# Artic.net
KiCad netlist of a schematic drawn in Altium Designer
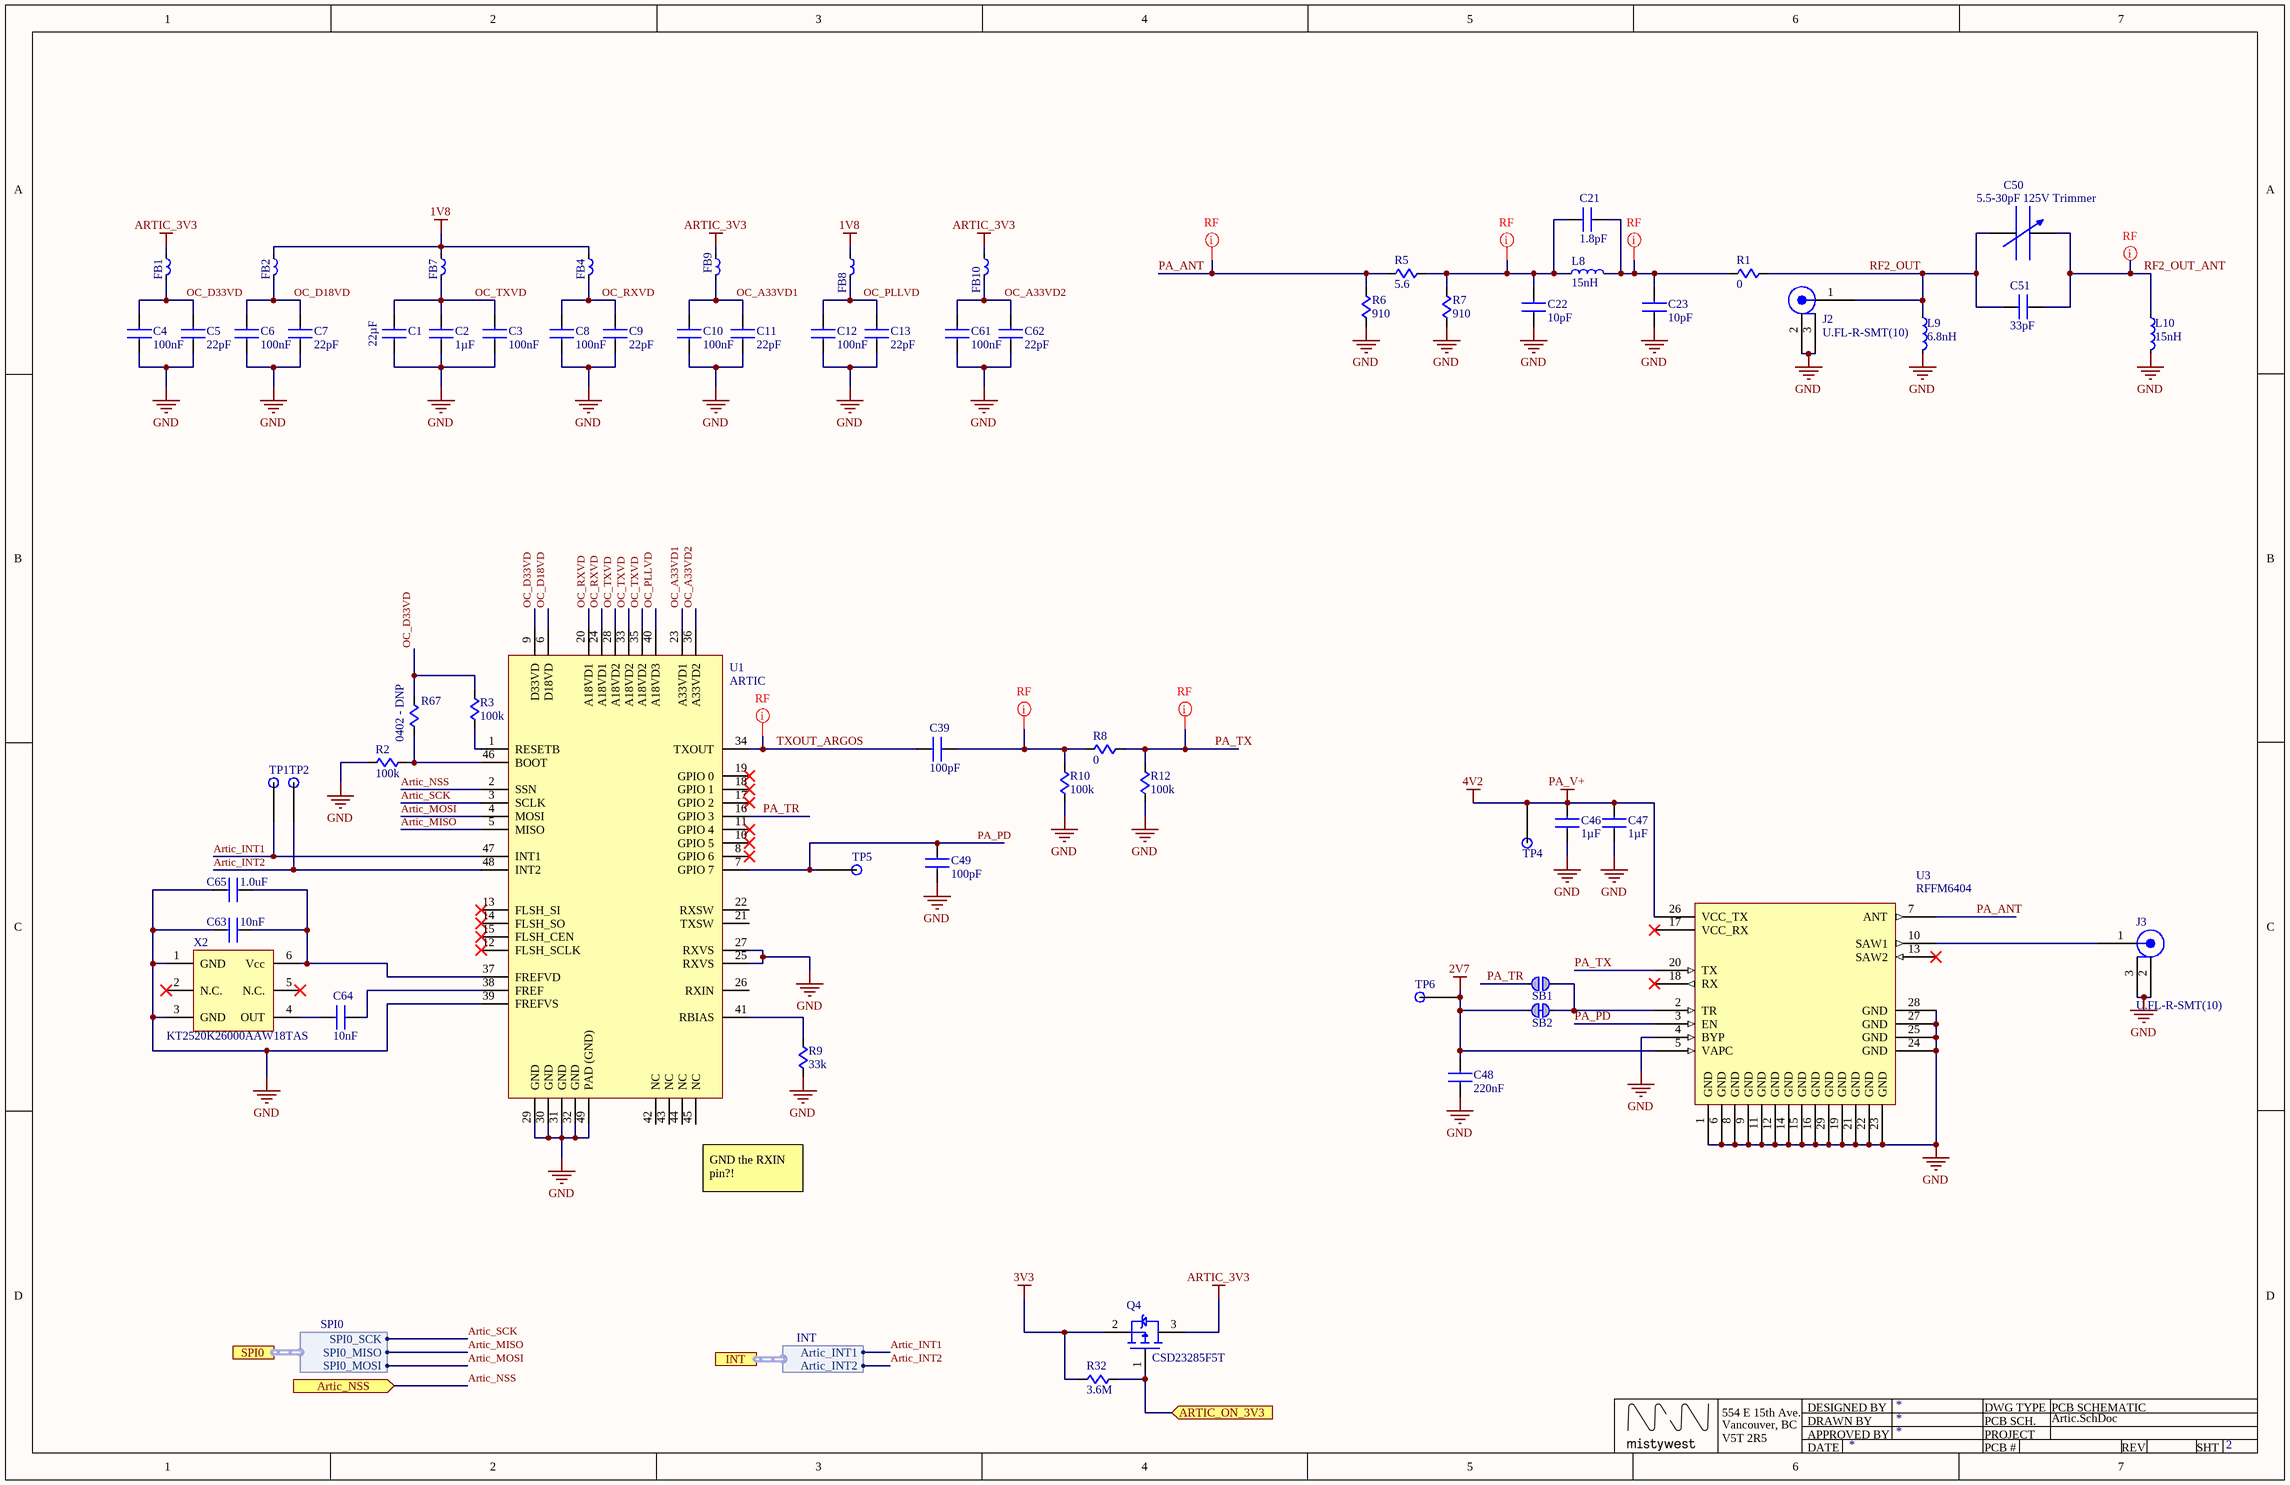
[diagram p0: Artic.SchDoc]

(export (version "E")
  (design (tool "Eeschema 10.0.6"))
  (components
    (comp (ref "C1")
      (value "22µF")
      (footprint "CAPC1608N-0603")
      (description "CAP CER 22UF 6.3V X5R 0603 ±10%")
      (fields
        (field (name "MANUFACTURER") "Samsung Electro-Mechanics America, Inc.")
        (field (name "MANUFACTURER PART NUMBER") "CL10A226KQ8NRNE")
      )
      (libsource (lib "Misty West") (part "Component_1"))
    )
    (comp (ref "C2")
      (value "1µF")
      (footprint "CAPC1005N-0402")
      (description "CAP CER 1UF 6.3V X7R 0402 ±10%")
      (fields
        (field (name "MANUFACTURER") "Samsung Electro-Mechanics America, Inc.")
        (field (name "MANUFACTURER PART NUMBER") "CL05B105KQ5NQNC")
      )
      (libsource (lib "Misty West") (part "Component_1"))
    )
    (comp (ref "C3")
      (value "100nF")
      (footprint "CAPC1005N-0402")
      (description "CAP CER 0.1UF 10V X7R 0402 ±5%")
      (fields
        (field (name "MANUFACTURER") "Samsung Electro-Mechanics America, Inc.")
        (field (name "MANUFACTURER PART NUMBER") "CL05B104JP5NNNC")
      )
      (libsource (lib "Misty West") (part "Component_1"))
    )
    (comp (ref "C4")
      (value "100nF")
      (footprint "CAPC1005N-0402")
      (description "CAP CER 0.1UF 10V X7R 0402 ±5%")
      (fields
        (field (name "MANUFACTURER") "Samsung Electro-Mechanics America, Inc.")
        (field (name "MANUFACTURER PART NUMBER") "CL05B104JP5NNNC")
      )
      (libsource (lib "Misty West") (part "Component_1"))
    )
    (comp (ref "C5")
      (value "22pF")
      (footprint "CAPC1005N-0402")
      (description "CAP CER 22PF 50V C0G/NP0 0402 ±5%")
      (fields
        (field (name "MANUFACTURER") "Samsung Electro-Mechanics America, Inc.")
        (field (name "MANUFACTURER PART NUMBER") "CL05C220JB5NNNC")
      )
      (libsource (lib "Misty West") (part "Component_1"))
    )
    (comp (ref "C6")
      (value "100nF")
      (footprint "CAPC1005N-0402")
      (description "CAP CER 0.1UF 10V X7R 0402 ±5%")
      (fields
        (field (name "MANUFACTURER") "Samsung Electro-Mechanics America, Inc.")
        (field (name "MANUFACTURER PART NUMBER") "CL05B104JP5NNNC")
      )
      (libsource (lib "Misty West") (part "Component_1"))
    )
    (comp (ref "C7")
      (value "22pF")
      (footprint "CAPC1005N-0402")
      (description "CAP CER 22PF 50V C0G/NP0 0402 ±5%")
      (fields
        (field (name "MANUFACTURER") "Samsung Electro-Mechanics America, Inc.")
        (field (name "MANUFACTURER PART NUMBER") "CL05C220JB5NNNC")
      )
      (libsource (lib "Misty West") (part "Component_1"))
    )
    (comp (ref "C8")
      (value "100nF")
      (footprint "CAPC1005N-0402")
      (description "CAP CER 0.1UF 10V X7R 0402 ±5%")
      (fields
        (field (name "MANUFACTURER") "Samsung Electro-Mechanics America, Inc.")
        (field (name "MANUFACTURER PART NUMBER") "CL05B104JP5NNNC")
      )
      (libsource (lib "Misty West") (part "Component_1"))
    )
    (comp (ref "C9")
      (value "22pF")
      (footprint "CAPC1005N-0402")
      (description "CAP CER 22PF 50V C0G/NP0 0402 ±5%")
      (fields
        (field (name "MANUFACTURER") "Samsung Electro-Mechanics America, Inc.")
        (field (name "MANUFACTURER PART NUMBER") "CL05C220JB5NNNC")
      )
      (libsource (lib "Misty West") (part "Component_1"))
    )
    (comp (ref "C10")
      (value "100nF")
      (footprint "CAPC1005N-0402")
      (description "CAP CER 0.1UF 10V X7R 0402 ±5%")
      (fields
        (field (name "MANUFACTURER") "Samsung Electro-Mechanics America, Inc.")
        (field (name "MANUFACTURER PART NUMBER") "CL05B104JP5NNNC")
      )
      (libsource (lib "Misty West") (part "Component_1"))
    )
    (comp (ref "C11")
      (value "22pF")
      (footprint "CAPC1005N-0402")
      (description "CAP CER 22PF 50V C0G/NP0 0402 ±5%")
      (fields
        (field (name "MANUFACTURER") "Samsung Electro-Mechanics America, Inc.")
        (field (name "MANUFACTURER PART NUMBER") "CL05C220JB5NNNC")
      )
      (libsource (lib "Misty West") (part "Component_1"))
    )
    (comp (ref "C12")
      (value "100nF")
      (footprint "CAPC1005N-0402")
      (description "CAP CER 0.1UF 10V X7R 0402 ±5%")
      (fields
        (field (name "MANUFACTURER") "Samsung Electro-Mechanics America, Inc.")
        (field (name "MANUFACTURER PART NUMBER") "CL05B104JP5NNNC")
      )
      (libsource (lib "Misty West") (part "Component_1"))
    )
    (comp (ref "C13")
      (value "22pF")
      (footprint "CAPC1005N-0402")
      (description "CAP CER 22PF 50V C0G/NP0 0402 ±5%")
      (fields
        (field (name "MANUFACTURER") "Samsung Electro-Mechanics America, Inc.")
        (field (name "MANUFACTURER PART NUMBER") "CL05C220JB5NNNC")
      )
      (libsource (lib "Misty West") (part "Component_1"))
    )
    (comp (ref "C21")
      (value "1.8pF")
      (footprint "CAPC1005N-0402")
      (description "CAP CER 1.8PF 50V C0G/NP0 0402 ±0.25pF")
      (fields
        (field (name "MANUFACTURER") "Samsung Electro-Mechanics America, Inc.")
        (field (name "MANUFACTURER PART NUMBER") "CL05C1R8CB5NNNC")
      )
      (libsource (lib "Misty West") (part "Component_1"))
    )
    (comp (ref "C22")
      (value "10pF")
      (footprint "CAPC1005N-0402")
      (description "CAP CER 10PF 50V C0G/NP0 0402 ±0.25pF")
      (fields
        (field (name "MANUFACTURER") "Samsung Electro-Mechanics America, Inc.")
        (field (name "MANUFACTURER PART NUMBER") "CL05C100CB5NNNC")
      )
      (libsource (lib "Misty West") (part "Component_1"))
    )
    (comp (ref "C23")
      (value "10pF")
      (footprint "CAPC1005N-0402")
      (description "CAP CER 10PF 50V C0G/NP0 0402 ±0.25pF")
      (fields
        (field (name "MANUFACTURER") "Samsung Electro-Mechanics America, Inc.")
        (field (name "MANUFACTURER PART NUMBER") "CL05C100CB5NNNC")
      )
      (libsource (lib "Misty West") (part "Component_1"))
    )
    (comp (ref "C39")
      (value "100pF")
      (footprint "CAPC1005N-0402")
      (description "CAP CER 100PF 50V C0G/NP0 0402 ±5% AEC-Q200")
      (fields
        (field (name "MANUFACTURER") "Samsung Electro-Mechanics America, Inc.")
        (field (name "MANUFACTURER PART NUMBER") "CL05C101JB51PNC")
      )
      (libsource (lib "Misty West") (part "Component_1"))
    )
    (comp (ref "C46")
      (value "1µF")
      (footprint "CAPC1005N-0402")
      (description "CAP CER 1UF 6.3V X7R 0402 ±10%")
      (fields
        (field (name "MANUFACTURER") "Samsung Electro-Mechanics America, Inc.")
        (field (name "MANUFACTURER PART NUMBER") "CL05B105KQ5NQNC")
      )
      (libsource (lib "Misty West") (part "Component_1"))
    )
    (comp (ref "C47")
      (value "1µF")
      (footprint "CAPC1005N-0402")
      (description "CAP CER 1UF 6.3V X7R 0402 ±10%")
      (fields
        (field (name "MANUFACTURER") "Samsung Electro-Mechanics America, Inc.")
        (field (name "MANUFACTURER PART NUMBER") "CL05B105KQ5NQNC")
      )
      (libsource (lib "Misty West") (part "Component_1"))
    )
    (comp (ref "C48")
      (value "220nF")
      (footprint "CAPC1005N-0402")
      (description "CAP CER 0.22UF 10V X7R 0402 ±10%")
      (fields
        (field (name "MANUFACTURER") "Samsung Electro-Mechanics America, Inc.")
        (field (name "MANUFACTURER PART NUMBER") "CL05B224KP5NNNC")
      )
      (libsource (lib "Misty West") (part "Component_1"))
    )
    (comp (ref "C49")
      (value "100pF")
      (footprint "CAPC1005N-0402")
      (description "CAP CER 100PF 50V C0G/NP0 0402 ±5% AEC-Q200")
      (fields
        (field (name "MANUFACTURER") "Samsung Electro-Mechanics America, Inc.")
        (field (name "MANUFACTURER PART NUMBER") "CL05C101JB51PNC")
      )
      (libsource (lib "Misty West") (part "Component_1"))
    )
    (comp (ref "C50")
      (value "5.5-30pF 125V Trimmer")
      (footprint "CAPC4531X17N")
      (description "CAP TRIMMER 5.5-30PF 125V SMD")
      (fields
        (field (name "MANUFACTURER") "Knowles Voltronics")
        (field (name "MANUFACTURER PART NUMBER") "JR300")
      )
      (libsource (lib "Misty West") (part "=Capacitance"))
    )
    (comp (ref "C51")
      (value "33pF")
      (footprint "CAPC1005N-0402")
      (description "CAP CER 33PF 50V C0G/NP0 0402 ±5%")
      (fields
        (field (name "TOLERANCE") "±5%")
        (field (name "VOLTAGE") "50V")
        (field (name "CAPACITANCE") "33pF")
      )
      (libsource (lib "Misty West") (part "Component_1"))
    )
    (comp (ref "C61")
      (value "100nF")
      (footprint "CAPC1005N-0402")
      (description "CAP CER 0.1UF 10V X7R 0402 ±5%")
      (fields
        (field (name "MANUFACTURER") "Samsung Electro-Mechanics America, Inc.")
        (field (name "MANUFACTURER PART NUMBER") "CL05B104JP5NNNC")
      )
      (libsource (lib "Misty West") (part "Component_1"))
    )
    (comp (ref "C62")
      (value "22pF")
      (footprint "CAPC1005N-0402")
      (description "CAP CER 22PF 50V C0G/NP0 0402 ±5%")
      (fields
        (field (name "MANUFACTURER") "Samsung Electro-Mechanics America, Inc.")
        (field (name "MANUFACTURER PART NUMBER") "CL05C220JB5NNNC")
      )
      (libsource (lib "Misty West") (part "Component_1"))
    )
    (comp (ref "C63")
      (value "10nF")
      (footprint "CAPC1005N-0402")
      (description "CAP CER 10000PF 10V X7R 0402 ±10%")
      (fields
        (field (name "MANUFACTURER") "Samsung Electro-Mechanics America, Inc.")
        (field (name "MANUFACTURER PART NUMBER") "CL05B103KP5NNNC")
      )
      (libsource (lib "Misty West") (part "Component_1"))
    )
    (comp (ref "C64")
      (value "10nF")
      (footprint "CAPC1005N-0402")
      (description "CAP CER 10000PF 10V X7R 0402 ±10%")
      (fields
        (field (name "MANUFACTURER") "Samsung Electro-Mechanics America, Inc.")
        (field (name "MANUFACTURER PART NUMBER") "CL05B103KP5NNNC")
      )
      (libsource (lib "Misty West") (part "Component_1"))
    )
    (comp (ref "C65")
      (value "1.0uF")
      (footprint "CAPC1608N-0603")
      (description "CAP CER 1.0uF 6.3V X7R 0603 ±10%")
      (fields
        (field (name "MANUFACTURER") "Samsung Electro-Mechanics America, Inc.")
        (field (name "MANUFACTURER PART NUMBER") "CL10B105KQ8NNN")
      )
      (libsource (lib "Misty West") (part "Component_1"))
    )
    (comp (ref "FB1")
      (value "BLM15AG221SN1D")
      (footprint "MURA-BLM15-CHIP-2_V")
      (fields (field (name "MANUFACTURER") "Murata"))
      (libsource (lib "Misty West") (part "CMP-04113-4"))
    )
    (comp (ref "FB2")
      (value "BLM15AG221SN1D")
      (footprint "MURA-BLM15-CHIP-2_V")
      (fields (field (name "MANUFACTURER") "Murata"))
      (libsource (lib "Misty West") (part "CMP-04113-4"))
    )
    (comp (ref "FB4")
      (value "BLM15AG221SN1D")
      (footprint "MURA-BLM15-CHIP-2_V")
      (fields (field (name "MANUFACTURER") "Murata"))
      (libsource (lib "Misty West") (part "CMP-04113-4"))
    )
    (comp (ref "FB7")
      (value "BLM15AG221SN1D")
      (footprint "MURA-BLM15-CHIP-2_V")
      (fields (field (name "MANUFACTURER") "Murata"))
      (libsource (lib "Misty West") (part "CMP-04113-4"))
    )
    (comp (ref "FB8")
      (value "BLM15AG221SN1D")
      (footprint "MURA-BLM15-CHIP-2_V")
      (fields (field (name "MANUFACTURER") "Murata"))
      (libsource (lib "Misty West") (part "CMP-04113-4"))
    )
    (comp (ref "FB9")
      (value "BLM15AG221SN1D")
      (footprint "MURA-BLM15-CHIP-2_V")
      (fields (field (name "MANUFACTURER") "Murata"))
      (libsource (lib "Misty West") (part "CMP-04113-4"))
    )
    (comp (ref "FB10")
      (value "BLM15AG221SN1D")
      (footprint "MURA-BLM15-CHIP-2_V")
      (fields (field (name "MANUFACTURER") "Murata"))
      (libsource (lib "Misty West") (part "CMP-04113-4"))
    )
    (comp (ref "J2")
      (value "CONNECTOR COAX-M 2GND")
      (footprint "con_hrs_U_FL-SMT")
      (description "CONN RECPT ULTRA-MINI COAX SMD")
      (fields
        (field (name "MFG") "HIROSE")
        (field (name "MFG_PN") "U.FL-R-SMT(10)")
        (field (name "MANUFACTURER PART NUMBER") "U.FL-R-SMT(10)")
      )
      (libsource (lib "Misty West") (part "CONNECTOR COAX-M 2GND"))
    )
    (comp (ref "J3")
      (value "CONNECTOR COAX-M 2GND")
      (footprint "con_hrs_U_FL-SMT")
      (description "CONN RECPT ULTRA-MINI COAX SMD")
      (fields
        (field (name "MFG") "HIROSE")
        (field (name "MFG_PN") "U.FL-R-SMT(10)")
        (field (name "MANUFACTURER PART NUMBER") "U.FL-R-SMT(10)")
      )
      (libsource (lib "Misty West") (part "CONNECTOR COAX-M 2GND"))
    )
    (comp (ref "L8")
      (value "15nH")
      (footprint "LQW2BA")
      (description "FIXED IND 15NH 1.5A 120 MOHM")
      (fields
        (field (name "MANUFACTURER") "MuRata")
        (field (name "MANUFACTURER PART NUMBER") "LQW2BAN15NG00L")
      )
      (libsource (lib "") (part "Component_1_3"))
    )
    (comp (ref "L9")
      (value "6.8nH")
      (footprint "0603HP")
      (description "0603HP-6N8X_E_")
      (fields (field (name "MANUFACTURER") "Coilcraft"))
      (libsource (lib "") (part "Component_1_3"))
    )
    (comp (ref "L10")
      (value "15nH")
      (footprint "0603HP")
      (description "0603HP-15NX_E_")
      (fields (field (name "MANUFACTURER") "Coilcraft"))
      (libsource (lib "") (part "Component_1_3"))
    )
    (comp (ref "Q4")
      (value "CSD23285F5T")
      (footprint "3-XFDFN")
      (description "P-Channel 12V 5.4A (Ta) 500mW (Ta) Surface Mount 3-PICOSTAR")
      (fields (field (name "MANUFACTURER") "Texas Instruments"))
      (libsource (lib "Misty West") (part "Mosfet-P-CH, 8Pin"))
    )
    (comp (ref "R1")
      (value "0")
      (footprint "RESC0402(1005)_N")
      (description "RES SMD 0.0OHM JUMPER 1/16W 0402")
      (fields
        (field (name "MANUFACTURER") "Yageo")
        (field (name "MANUFACTURER PART NUMBER") "RC0402JR-070RL")
      )
      (libsource (lib "") (part "Component_1_1"))
    )
    (comp (ref "R2")
      (value "100k")
      (footprint "RESC0402(1005)_N")
      (description "RES SMD 100K OHM 1% 1/10W 0402")
      (fields
        (field (name "MANUFACTURER") "Panasonic Electronic Components")
        (field (name "MANUFACTURER PART NUMBER") "ERJ-2RKF1003X")
      )
      (libsource (lib "") (part "Component_1_1"))
    )
    (comp (ref "R3")
      (value "100k")
      (footprint "RESC0402(1005)_N")
      (description "RES SMD 100K OHM 1% 1/10W 0402")
      (fields
        (field (name "MANUFACTURER") "Panasonic Electronic Components")
        (field (name "MANUFACTURER PART NUMBER") "ERJ-2RKF1003X")
      )
      (libsource (lib "") (part "Component_1_1"))
    )
    (comp (ref "R5")
      (value "5.6")
      (footprint "Chip Res 1608_0603 MMC")
      (description "RES SMD 5.6 OHM 1% 1/4W 0603")
      (fields
        (field (name "MANUFACTURER") "Panasonic")
        (field (name "MANUFACTURER PART NUMBER") "ERJ-3BQF5R6V")
      )
      (libsource (lib "") (part "Component_1_2"))
    )
    (comp (ref "R6")
      (value "910")
      (footprint "Chip Res 1608_0603 MMC")
      (description "PANASONIC   ERJPA3F9100V   RESISTOR, ERJP, 910 OHM, 0603, 0.25W, 1%")
      (fields
        (field (name "MANUFACTURER") "Panasonic")
        (field (name "MANUFACTURER PART NUMBER") "ERJ-PA3F9100V")
      )
      (libsource (lib "") (part "Component_1_2"))
    )
    (comp (ref "R7")
      (value "910")
      (footprint "Chip Res 1608_0603 MMC")
      (description "PANASONIC   ERJPA3F9100V   RESISTOR, ERJP, 910 OHM, 0603, 0.25W, 1%")
      (fields
        (field (name "MANUFACTURER") "Panasonic")
        (field (name "MANUFACTURER PART NUMBER") "ERJ-PA3F9100V")
      )
      (libsource (lib "") (part "Component_1_2"))
    )
    (comp (ref "R8")
      (value "0")
      (footprint "RESC0402(1005)_N")
      (description "RES SMD 0.0OHM JUMPER 1/16W 0402")
      (fields
        (field (name "MANUFACTURER") "Yageo")
        (field (name "MANUFACTURER PART NUMBER") "RC0402JR-070RL")
      )
      (libsource (lib "") (part "Component_1_1"))
    )
    (comp (ref "R9")
      (value "33k")
      (footprint "RESC0402(1005)_N")
      (description "RES SMD 33K OHM 1% 1/10W 0402")
      (fields
        (field (name "MANUFACTURER") "Panasonic Electronic Components")
        (field (name "MANUFACTURER PART NUMBER") "ERJ-2RKF3302X")
      )
      (libsource (lib "") (part "Component_1_1"))
    )
    (comp (ref "R10")
      (value "100k")
      (footprint "RESC0402(1005)_N")
      (description "RES SMD 100K OHM 1% 1/10W 0402")
      (fields
        (field (name "MANUFACTURER") "Panasonic Electronic Components")
        (field (name "MANUFACTURER PART NUMBER") "ERJ-2RKF1003X")
      )
      (libsource (lib "") (part "Component_1_1"))
    )
    (comp (ref "R12")
      (value "100k")
      (footprint "RESC0402(1005)_N")
      (description "RES SMD 100K OHM 1% 1/10W 0402")
      (fields
        (field (name "MANUFACTURER") "Panasonic Electronic Components")
        (field (name "MANUFACTURER PART NUMBER") "ERJ-2RKF1003X")
      )
      (libsource (lib "") (part "Component_1_1"))
    )
    (comp (ref "R32")
      (value "3.6M")
      (footprint "RESC0402(1005)_N")
      (description "RES SMD 3.6M OHM 1% 1/16W 0402")
      (fields
        (field (name "MANUFACTURER") "Yageo")
        (field (name "MANUFACTURER PART NUMBER") "RC0402FR-073M6L")
      )
      (libsource (lib "") (part "Component_1_1"))
    )
    (comp (ref "R67")
      (value "0402 - DNP")
      (footprint "RESC0402(1005)_N")
      (libsource (lib "") (part "Component_1_1"))
    )
    (comp (ref "SB1")
      (value "Solder Bridge Open - 50mil")
      (footprint "Solder_Bridge_Open_50")
      (description "Open Solder Bridge (50mil size)")
      (libsource (lib "Misty West") (part "SB_Open"))
    )
    (comp (ref "SB2")
      (value "Solder Bridge Closed - 50mil")
      (footprint "Solder_Bridge_Closed_50")
      (description "Closed Solder Bridge (50mil size)")
      (libsource (lib "Misty West") (part "SB_Closed"))
    )
    (comp (ref "TP1")
      (value "~")
      (footprint "Testpoint_16mil_32mil")
      (description "Test Point - 16mil/32mil via")
      (libsource (lib "Misty West") (part "TestPoint_NoPart"))
    )
    (comp (ref "TP2")
      (value "~")
      (footprint "Testpoint_16mil_32mil")
      (description "Test Point - 16mil/32mil via")
      (libsource (lib "Misty West") (part "TestPoint_NoPart"))
    )
    (comp (ref "TP4")
      (value "~")
      (footprint "Testpoint_16mil_32mil")
      (description "Test Point - 16mil/32mil via")
      (libsource (lib "Misty West") (part "TestPoint_NoPart"))
    )
    (comp (ref "TP5")
      (value "~")
      (footprint "Testpoint_16mil_32mil")
      (description "Test Point - 16mil/32mil via")
      (libsource (lib "Misty West") (part "TestPoint_NoPart"))
    )
    (comp (ref "TP6")
      (value "~")
      (footprint "Testpoint_16mil_32mil")
      (description "Test Point - 16mil/32mil via")
      (libsource (lib "Misty West") (part "TestPoint_NoPart"))
    )
    (comp (ref "U1")
      (value "ARTIC")
      (footprint "QFN, 48-Lead")
      (description "Ansem ARTIC")
      (fields (field (name "MANUFACTURER") "Ansem"))
      (libsource (lib "Misty West") (part "Ansem Artic 2"))
    )
    (comp (ref "U3")
      (value "RFFM6404")
      (footprint "LGA28C100P8X8_600X600X105")
      (description "Transmit/Receive Module, 2.5V to 4.5V, ISM Band, 27.5dBm, 430MHz to 450MHz")
      (fields (field (name "MANUFACTURER") "Qorvo") (field (name "MANUFACTURER PART NUMBER") "RFFM6404TR13"))
      (libsource (lib "Misty West") (part "RFFM6404"))
    )
    (comp (ref "X2")
      (value "KT2520K26000AAW18TAS")
      (footprint "KT2520")
      (description "26MHz TCXO Clipped Sine Wave Oscillator 1.8V 6-SMD, No Lead")
      (fields (field (name "MANUFACTURER") "Kyocera International Inc. Electronic Components"))
      (libsource (lib "") (part "Component_1_4"))
    )
  )
  (nets
    (net (code "3") (name "/ARTIC_ON_3V3") (class "Default")
      (node (ref "Q4") (pin "1") (pinfunction "Gate_1") (pintype "passive"))
      (node (ref "R32") (pin "2") (pintype "passive"))
    )
    (net (code "4") (name "/Artic_INT1") (class "Default")
      (node (ref "TP1") (pin "TP") (pinfunction "TP_TP") (pintype "passive"))
      (node (ref "U1") (pin "47") (pinfunction "INT1_47") (pintype "passive"))
    )
    (net (code "5") (name "/Artic_INT2") (class "Default")
      (node (ref "TP2") (pin "TP") (pinfunction "TP_TP") (pintype "passive"))
      (node (ref "U1") (pin "48") (pinfunction "INT2_48") (pintype "passive"))
    )
    (net (code "6") (name "/Artic_MISO") (class "Default")
      (node (ref "U1") (pin "5") (pinfunction "MISO_5") (pintype "passive"))
    )
    (net (code "7") (name "/Artic_MOSI") (class "Default")
      (node (ref "U1") (pin "4") (pinfunction "MOSI_4") (pintype "passive"))
    )
    (net (code "8") (name "/Artic_NSS") (class "Default")
      (node (ref "U1") (pin "2") (pinfunction "SSN_2") (pintype "passive"))
    )
    (net (code "9") (name "/Artic_SCK") (class "Default")
      (node (ref "U1") (pin "3") (pinfunction "SCLK_3") (pintype "passive"))
    )
    (net (code "10") (name "/OC_A33VD1") (class "Default")
      (node (ref "C10") (pin "1") (pintype "passive"))
      (node (ref "C11") (pin "1") (pintype "passive"))
      (node (ref "FB9") (pin "2") (pinfunction "2_2") (pintype "passive"))
      (node (ref "U1") (pin "23") (pinfunction "A33VD1_23") (pintype "passive"))
    )
    (net (code "11") (name "/OC_A33VD2") (class "Default")
      (node (ref "C61") (pin "1") (pintype "passive"))
      (node (ref "C62") (pin "1") (pintype "passive"))
      (node (ref "FB10") (pin "2") (pinfunction "2_2") (pintype "passive"))
      (node (ref "U1") (pin "36") (pinfunction "A33VD2_36") (pintype "passive"))
    )
    (net (code "12") (name "/OC_D18VD") (class "Default")
      (node (ref "C6") (pin "1") (pintype "passive"))
      (node (ref "C7") (pin "1") (pintype "passive"))
      (node (ref "FB2") (pin "2") (pinfunction "2_2") (pintype "passive"))
      (node (ref "U1") (pin "6") (pinfunction "D18VD_6") (pintype "passive"))
    )
    (net (code "13") (name "/OC_D33VD") (class "Default")
      (node (ref "C4") (pin "1") (pintype "passive"))
      (node (ref "C5") (pin "1") (pintype "passive"))
      (node (ref "FB1") (pin "2") (pinfunction "2_2") (pintype "passive"))
      (node (ref "R3") (pin "2") (pintype "passive"))
      (node (ref "R67") (pin "2") (pintype "passive"))
      (node (ref "U1") (pin "9") (pinfunction "D33VD_9") (pintype "passive"))
    )
    (net (code "14") (name "/OC_PLLVD") (class "Default")
      (node (ref "C12") (pin "1") (pintype "passive"))
      (node (ref "C13") (pin "1") (pintype "passive"))
      (node (ref "FB8") (pin "2") (pinfunction "2_2") (pintype "passive"))
      (node (ref "U1") (pin "40") (pinfunction "A18VD3_40") (pintype "passive"))
    )
    (net (code "15") (name "/OC_RXVD") (class "Default")
      (node (ref "C8") (pin "1") (pintype "passive"))
      (node (ref "C9") (pin "1") (pintype "passive"))
      (node (ref "FB4") (pin "2") (pinfunction "2_2") (pintype "passive"))
      (node (ref "U1") (pin "20") (pinfunction "A18VD1_20") (pintype "passive"))
      (node (ref "U1") (pin "24") (pinfunction "A18VD1_24") (pintype "passive"))
    )
    (net (code "16") (name "/OC_TXVD") (class "Default")
      (node (ref "C1") (pin "1") (pintype "passive"))
      (node (ref "C2") (pin "1") (pintype "passive"))
      (node (ref "C3") (pin "1") (pintype "passive"))
      (node (ref "FB7") (pin "2") (pinfunction "2_2") (pintype "passive"))
      (node (ref "U1") (pin "28") (pinfunction "A18VD2_28") (pintype "passive"))
      (node (ref "U1") (pin "33") (pinfunction "A18VD2_33") (pintype "passive"))
      (node (ref "U1") (pin "35") (pinfunction "A18VD2_35") (pintype "passive"))
    )
    (net (code "17") (name "/PA_ANT") (class "Default")
      (node (ref "R5") (pin "1") (pinfunction "1_1") (pintype "passive"))
      (node (ref "R6") (pin "2") (pinfunction "2_2") (pintype "passive"))
      (node (ref "U3") (pin "7") (pinfunction "ANT_7") (pintype "output"))
    )
    (net (code "18") (name "/PA_PD") (class "Default")
      (node (ref "C49") (pin "2") (pintype "passive"))
      (node (ref "TP5") (pin "TP") (pinfunction "TP_TP") (pintype "passive"))
      (node (ref "U1") (pin "7") (pinfunction "GPIO_7_7") (pintype "passive"))
      (node (ref "U3") (pin "3") (pinfunction "EN_3") (pintype "input"))
    )
    (net (code "19") (name "/PA_TR") (class "Default")
      (node (ref "SB1") (pin "2") (pinfunction "2_2") (pintype "passive"))
      (node (ref "U1") (pin "16") (pinfunction "GPIO_3_16") (pintype "passive"))
    )
    (net (code "20") (name "/PA_TX") (class "Default")
      (node (ref "R12") (pin "2") (pintype "passive"))
      (node (ref "R8") (pin "2") (pintype "passive"))
      (node (ref "U3") (pin "20") (pinfunction "TX_20") (pintype "input"))
    )
    (net (code "21") (name "/RF2_OUT") (class "Default")
      (node (ref "C50") (pin "1") (pinfunction "1_1") (pintype "passive"))
      (node (ref "C51") (pin "1") (pintype "passive"))
      (node (ref "J2") (pin "1") (pinfunction "CENTER_1") (pintype "passive"))
      (node (ref "L9") (pin "1") (pinfunction "1_1") (pintype "passive"))
      (node (ref "R1") (pin "2") (pintype "passive"))
    )
    (net (code "22") (name "/RF2_OUT_ANT") (class "Default")
      (node (ref "C50") (pin "2") (pinfunction "2_2") (pintype "passive"))
      (node (ref "C51") (pin "2") (pintype "passive"))
      (node (ref "L10") (pin "1") (pinfunction "1_1") (pintype "passive"))
    )
    (net (code "23") (name "/TXOUT_ARGOS") (class "Default")
      (node (ref "C39") (pin "1") (pintype "passive"))
      (node (ref "U1") (pin "34") (pinfunction "TXOUT_34") (pintype "passive"))
    )
    (net (code "26") (name "1V8") (class "Default")
      (node (ref "FB2") (pin "1") (pinfunction "1_1") (pintype "passive"))
      (node (ref "FB4") (pin "1") (pinfunction "1_1") (pintype "passive"))
      (node (ref "FB7") (pin "1") (pinfunction "1_1") (pintype "passive"))
      (node (ref "FB8") (pin "1") (pinfunction "1_1") (pintype "passive"))
    )
    (net (code "27") (name "2V7") (class "Default")
      (node (ref "C48") (pin "1") (pintype "passive"))
      (node (ref "SB2") (pin "2") (pinfunction "2_2") (pintype "passive"))
      (node (ref "TP6") (pin "TP") (pinfunction "TP_TP") (pintype "passive"))
      (node (ref "U3") (pin "5") (pinfunction "VAPC_5") (pintype "input"))
    )
    (net (code "28") (name "3V3") (class "Default")
      (node (ref "Q4") (pin "2") (pinfunction "Source_2") (pintype "passive"))
      (node (ref "R32") (pin "1") (pintype "passive"))
    )
    (net (code "29") (name "4V2") (class "Default")
      (node (ref "C46") (pin "1") (pintype "passive"))
      (node (ref "C47") (pin "1") (pintype "passive"))
      (node (ref "TP4") (pin "TP") (pinfunction "TP_TP") (pintype "passive"))
      (node (ref "U3") (pin "26") (pinfunction "VCC_TX_26") (pintype "power_in"))
    )
    (net (code "30") (name "ARTIC_3V3") (class "Default")
      (node (ref "FB1") (pin "1") (pinfunction "1_1") (pintype "passive"))
      (node (ref "FB10") (pin "1") (pinfunction "1_1") (pintype "passive"))
      (node (ref "FB9") (pin "1") (pinfunction "1_1") (pintype "passive"))
      (node (ref "Q4") (pin "3") (pinfunction "Drain_3") (pintype "passive"))
    )
    (net (code "31") (name "GND") (class "Default")
      (node (ref "C1") (pin "2") (pintype "passive"))
      (node (ref "C10") (pin "2") (pintype "passive"))
      (node (ref "C11") (pin "2") (pintype "passive"))
      (node (ref "C12") (pin "2") (pintype "passive"))
      (node (ref "C13") (pin "2") (pintype "passive"))
      (node (ref "C2") (pin "2") (pintype "passive"))
      (node (ref "C22") (pin "2") (pintype "passive"))
      (node (ref "C23") (pin "2") (pintype "passive"))
      (node (ref "C3") (pin "2") (pintype "passive"))
      (node (ref "C4") (pin "2") (pintype "passive"))
      (node (ref "C46") (pin "2") (pintype "passive"))
      (node (ref "C47") (pin "2") (pintype "passive"))
      (node (ref "C48") (pin "2") (pintype "passive"))
      (node (ref "C49") (pin "1") (pintype "passive"))
      (node (ref "C5") (pin "2") (pintype "passive"))
      (node (ref "C6") (pin "2") (pintype "passive"))
      (node (ref "C61") (pin "2") (pintype "passive"))
      (node (ref "C62") (pin "2") (pintype "passive"))
      (node (ref "C63") (pin "1") (pintype "passive"))
      (node (ref "C65") (pin "1") (pintype "passive"))
      (node (ref "C7") (pin "2") (pintype "passive"))
      (node (ref "C8") (pin "2") (pintype "passive"))
      (node (ref "C9") (pin "2") (pintype "passive"))
      (node (ref "J2") (pin "2") (pinfunction "SHIELD_2") (pintype "passive"))
      (node (ref "J2") (pin "3") (pinfunction "SHIELD2_3") (pintype "passive"))
      (node (ref "J3") (pin "2") (pinfunction "SHIELD_2") (pintype "passive"))
      (node (ref "J3") (pin "3") (pinfunction "SHIELD2_3") (pintype "passive"))
      (node (ref "L10") (pin "2") (pinfunction "2_2") (pintype "passive"))
      (node (ref "L9") (pin "2") (pinfunction "2_2") (pintype "passive"))
      (node (ref "R10") (pin "1") (pintype "passive"))
      (node (ref "R12") (pin "1") (pintype "passive"))
      (node (ref "R2") (pin "2") (pintype "passive"))
      (node (ref "R6") (pin "1") (pinfunction "1_1") (pintype "passive"))
      (node (ref "R7") (pin "1") (pinfunction "1_1") (pintype "passive"))
      (node (ref "R9") (pin "1") (pintype "passive"))
      (node (ref "U1") (pin "25") (pinfunction "RXVS_25") (pintype "passive"))
      (node (ref "U1") (pin "27") (pinfunction "RXVS_27") (pintype "passive"))
      (node (ref "U1") (pin "29") (pinfunction "GND_29") (pintype "passive"))
      (node (ref "U1") (pin "30") (pinfunction "GND_30") (pintype "passive"))
      (node (ref "U1") (pin "31") (pinfunction "GND_31") (pintype "passive"))
      (node (ref "U1") (pin "32") (pinfunction "GND_32") (pintype "passive"))
      (node (ref "U1") (pin "39") (pinfunction "FREFVS_39") (pintype "passive"))
      (node (ref "U1") (pin "49") (pinfunction "PAD_(GND)_49") (pintype "passive"))
      (node (ref "U3") (pin "1") (pinfunction "GND_1") (pintype "power_in"))
      (node (ref "U3") (pin "11") (pinfunction "GND_11") (pintype "power_in"))
      (node (ref "U3") (pin "12") (pinfunction "GND_12") (pintype "power_in"))
      (node (ref "U3") (pin "14") (pinfunction "GND_14") (pintype "power_in"))
      (node (ref "U3") (pin "15") (pinfunction "GND_15") (pintype "power_in"))
      (node (ref "U3") (pin "16") (pinfunction "GND_16") (pintype "power_in"))
      (node (ref "U3") (pin "19") (pinfunction "GND_19") (pintype "power_in"))
      (node (ref "U3") (pin "21") (pinfunction "GND_21") (pintype "power_in"))
      (node (ref "U3") (pin "22") (pinfunction "GND_22") (pintype "power_in"))
      (node (ref "U3") (pin "23") (pinfunction "GND_23") (pintype "power_in"))
      (node (ref "U3") (pin "24") (pinfunction "GND_24") (pintype "power_in"))
      (node (ref "U3") (pin "25") (pinfunction "GND_25") (pintype "power_in"))
      (node (ref "U3") (pin "27") (pinfunction "GND_27") (pintype "power_in"))
      (node (ref "U3") (pin "28") (pinfunction "GND_28") (pintype "power_in"))
      (node (ref "U3") (pin "29") (pinfunction "GND_29") (pintype "power_in"))
      (node (ref "U3") (pin "4") (pinfunction "BYP_4") (pintype "input"))
      (node (ref "U3") (pin "6") (pinfunction "GND_6") (pintype "power_in"))
      (node (ref "U3") (pin "8") (pinfunction "GND_8") (pintype "power_in"))
      (node (ref "U3") (pin "9") (pinfunction "GND_9") (pintype "power_in"))
      (node (ref "X2") (pin "1") (pinfunction "GND_1") (pintype "passive"))
      (node (ref "X2") (pin "3") (pinfunction "GND_3") (pintype "passive"))
    )
    (net (code "32") (name "Net-(C21-Pad1)") (class "Default")
      (node (ref "C21") (pin "1") (pintype "passive"))
      (node (ref "C22") (pin "1") (pintype "passive"))
      (node (ref "L8") (pin "1") (pinfunction "1_1") (pintype "passive"))
      (node (ref "R5") (pin "2") (pinfunction "2_2") (pintype "passive"))
      (node (ref "R7") (pin "2") (pinfunction "2_2") (pintype "passive"))
    )
    (net (code "33") (name "Net-(C21-Pad2)") (class "Default")
      (node (ref "C21") (pin "2") (pintype "passive"))
      (node (ref "C23") (pin "1") (pintype "passive"))
      (node (ref "L8") (pin "2") (pinfunction "2_2") (pintype "passive"))
      (node (ref "R1") (pin "1") (pintype "passive"))
    )
    (net (code "34") (name "Net-(C39-Pad2)") (class "Default")
      (node (ref "C39") (pin "2") (pintype "passive"))
      (node (ref "R10") (pin "2") (pintype "passive"))
      (node (ref "R8") (pin "1") (pintype "passive"))
    )
    (net (code "35") (name "Net-(J3-CENTER)") (class "Default")
      (node (ref "J3") (pin "1") (pinfunction "CENTER_1") (pintype "passive"))
      (node (ref "U3") (pin "10") (pinfunction "SAW1_10") (pintype "output"))
    )
    (net (code "36") (name "Net-(U1-BOOT)") (class "Default")
      (node (ref "R2") (pin "1") (pintype "passive"))
      (node (ref "R67") (pin "1") (pintype "passive"))
      (node (ref "U1") (pin "46") (pinfunction "BOOT_46") (pintype "passive"))
    )
    (net (code "37") (name "Net-(U1-FREF)") (class "Default")
      (node (ref "C64") (pin "2") (pintype "passive"))
      (node (ref "U1") (pin "38") (pinfunction "FREF_38") (pintype "passive"))
    )
    (net (code "38") (name "Net-(U1-FREFVD)") (class "Default")
      (node (ref "C63") (pin "2") (pintype "passive"))
      (node (ref "C65") (pin "2") (pintype "passive"))
      (node (ref "U1") (pin "37") (pinfunction "FREFVD_37") (pintype "passive"))
      (node (ref "X2") (pin "6") (pinfunction "Vcc_6") (pintype "passive"))
    )
    (net (code "39") (name "Net-(U1-RBIAS)") (class "Default")
      (node (ref "R9") (pin "2") (pintype "passive"))
      (node (ref "U1") (pin "41") (pinfunction "RBIAS_41") (pintype "passive"))
    )
    (net (code "40") (name "Net-(U1-RESETB)") (class "Default")
      (node (ref "R3") (pin "1") (pintype "passive"))
      (node (ref "U1") (pin "1") (pinfunction "RESETB_1") (pintype "passive"))
    )
    (net (code "41") (name "Net-(U3-TR)") (class "Default")
      (node (ref "SB1") (pin "1") (pinfunction "1_1") (pintype "passive"))
      (node (ref "SB2") (pin "1") (pinfunction "1_1") (pintype "passive"))
      (node (ref "U3") (pin "2") (pinfunction "TR_2") (pintype "input"))
    )
    (net (code "42") (name "Net-(X2-OUT)") (class "Default")
      (node (ref "C64") (pin "1") (pintype "passive"))
      (node (ref "X2") (pin "4") (pinfunction "OUT_4") (pintype "passive"))
    )
    (net (code "43") (name "unconnected-(U1-FLSH_CEN-Pad15)") (class "Default")
      (node (ref "U1") (pin "15") (pinfunction "FLSH_CEN_15") (pintype "passive+no_connect"))
    )
    (net (code "44") (name "unconnected-(U1-FLSH_SCLK-Pad12)") (class "Default")
      (node (ref "U1") (pin "12") (pinfunction "FLSH_SCLK_12") (pintype "passive+no_connect"))
    )
    (net (code "45") (name "unconnected-(U1-FLSH_SI-Pad13)") (class "Default")
      (node (ref "U1") (pin "13") (pinfunction "FLSH_SI_13") (pintype "passive+no_connect"))
    )
    (net (code "46") (name "unconnected-(U1-FLSH_SO-Pad14)") (class "Default")
      (node (ref "U1") (pin "14") (pinfunction "FLSH_SO_14") (pintype "passive+no_connect"))
    )
    (net (code "47") (name "unconnected-(U1-GPIO_0-Pad19)") (class "Default")
      (node (ref "U1") (pin "19") (pinfunction "GPIO_0_19") (pintype "passive+no_connect"))
    )
    (net (code "48") (name "unconnected-(U1-GPIO_1-Pad18)") (class "Default")
      (node (ref "U1") (pin "18") (pinfunction "GPIO_1_18") (pintype "passive+no_connect"))
    )
    (net (code "49") (name "unconnected-(U1-GPIO_2-Pad17)") (class "Default")
      (node (ref "U1") (pin "17") (pinfunction "GPIO_2_17") (pintype "passive+no_connect"))
    )
    (net (code "50") (name "unconnected-(U1-GPIO_4-Pad11)") (class "Default")
      (node (ref "U1") (pin "11") (pinfunction "GPIO_4_11") (pintype "passive+no_connect"))
    )
    (net (code "51") (name "unconnected-(U1-GPIO_5-Pad10)") (class "Default")
      (node (ref "U1") (pin "10") (pinfunction "GPIO_5_10") (pintype "passive+no_connect"))
    )
    (net (code "52") (name "unconnected-(U1-GPIO_6-Pad8)") (class "Default")
      (node (ref "U1") (pin "8") (pinfunction "GPIO_6_8") (pintype "passive+no_connect"))
    )
    (net (code "53") (name "unconnected-(U1-NC-Pad42)") (class "Default")
      (node (ref "U1") (pin "42") (pinfunction "NC_42") (pintype "passive"))
    )
    (net (code "54") (name "unconnected-(U1-NC-Pad43)") (class "Default")
      (node (ref "U1") (pin "43") (pinfunction "NC_43") (pintype "passive"))
    )
    (net (code "55") (name "unconnected-(U1-NC-Pad44)") (class "Default")
      (node (ref "U1") (pin "44") (pinfunction "NC_44") (pintype "passive"))
    )
    (net (code "56") (name "unconnected-(U1-NC-Pad45)") (class "Default")
      (node (ref "U1") (pin "45") (pinfunction "NC_45") (pintype "passive"))
    )
    (net (code "57") (name "unconnected-(U1-RXIN-Pad26)") (class "Default")
      (node (ref "U1") (pin "26") (pinfunction "RXIN_26") (pintype "passive"))
    )
    (net (code "58") (name "unconnected-(U1-RXSW-Pad22)") (class "Default")
      (node (ref "U1") (pin "22") (pinfunction "RXSW_22") (pintype "passive"))
    )
    (net (code "59") (name "unconnected-(U1-TXSW-Pad21)") (class "Default")
      (node (ref "U1") (pin "21") (pinfunction "TXSW_21") (pintype "passive"))
    )
    (net (code "60") (name "unconnected-(U3-RX-Pad18)") (class "Default")
      (node (ref "U3") (pin "18") (pinfunction "RX_18") (pintype "output+no_connect"))
    )
    (net (code "61") (name "unconnected-(U3-SAW2-Pad13)") (class "Default")
      (node (ref "U3") (pin "13") (pinfunction "SAW2_13") (pintype "input+no_connect"))
    )
    (net (code "62") (name "unconnected-(U3-VCC_RX-Pad17)") (class "Default")
      (node (ref "U3") (pin "17") (pinfunction "VCC_RX_17") (pintype "power_in+no_connect"))
    )
    (net (code "63") (name "unconnected-(X2-N.C.-Pad2)") (class "Default")
      (node (ref "X2") (pin "2") (pinfunction "N.C._2") (pintype "passive+no_connect"))
    )
    (net (code "64") (name "unconnected-(X2-N.C.-Pad5)") (class "Default")
      (node (ref "X2") (pin "5") (pinfunction "N.C._5") (pintype "passive+no_connect"))
    )
  )
)
